# CLK_GEN.net
KiCad netlist of a schematic drawn in Altium Designer
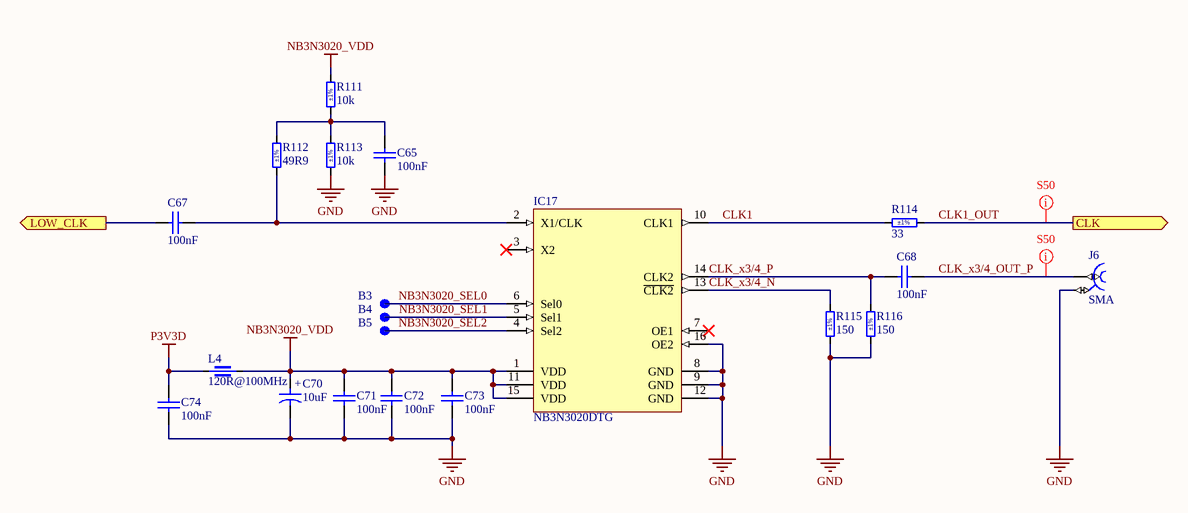
[diagram p0: CLK_GEN.SchDoc]

(export (version "E")
  (design (tool "Eeschema 10.0.6"))
  (components
    (comp (ref "B3")
      (value "SMD Pad")
      (footprint "C100")
      (description "Pad")
      (fields (field (name "PART NUMBER") "SMD_PAD_D1MM") (field (name "AUTHOR") "CERN DEM JLC"))
      (libsource (lib "Eletro-mechanical") (part "Single SMD Pad (Round)"))
    )
    (comp (ref "B4")
      (value "SMD Pad")
      (footprint "C100")
      (description "Pad")
      (fields (field (name "PART NUMBER") "SMD_PAD_D1MM") (field (name "AUTHOR") "CERN DEM JLC"))
      (libsource (lib "Eletro-mechanical") (part "Single SMD Pad (Round)"))
    )
    (comp (ref "B5")
      (value "SMD Pad")
      (footprint "C100")
      (description "Pad")
      (fields (field (name "PART NUMBER") "SMD_PAD_D1MM") (field (name "AUTHOR") "CERN DEM JLC"))
      (libsource (lib "Eletro-mechanical") (part "Single SMD Pad (Round)"))
    )
    (comp (ref "C65")
      (value "100nF")
      (footprint "CAPC1005X55N")
      (description "Non-polarised capacitor")
      (fields
        (field (name "PART NUMBER") "CC0402_100NF_50V_10%_X7R")
        (field (name "VOLTAGE") "50V")
        (field (name "AUTHOR") "CERN DEM MR")
      )
      (libsource (lib "Capacitors") (part "Capacitor - non polarized"))
    )
    (comp (ref "C67")
      (value "100nF")
      (footprint "CAPC1005X55N")
      (description "Non-polarised capacitor")
      (fields
        (field (name "PART NUMBER") "CC0402_100NF_50V_10%_X7R")
        (field (name "VOLTAGE") "50V")
        (field (name "AUTHOR") "CERN DEM MR")
      )
      (libsource (lib "Capacitors") (part "Capacitor - non polarized"))
    )
    (comp (ref "C68")
      (value "100nF")
      (footprint "CAPC1005X55N")
      (description "Non-polarised capacitor")
      (fields
        (field (name "PART NUMBER") "CC0402_100NF_50V_10%_X7R")
        (field (name "VOLTAGE") "50V")
        (field (name "AUTHOR") "CERN DEM MR")
      )
      (libsource (lib "Capacitors") (part "Capacitor - non polarized"))
    )
    (comp (ref "C70")
      (value "10uF")
      (footprint "CAPMP3216X180N")
      (description "Polarised capacitor")
      (fields
        (field (name "PART NUMBER") "CTE3216-18_10UF_16V_20%_AVX_TCJ")
        (field (name "VOLTAGE") "16V")
        (field (name "AUTHOR") "CERN DEM JLC")
      )
      (libsource (lib "Capacitors") (part "Capacitor - polarized"))
    )
    (comp (ref "C71")
      (value "100nF")
      (footprint "CAPC1005X55N")
      (description "Non-polarised capacitor")
      (fields
        (field (name "PART NUMBER") "CC0402_100NF_50V_10%_X7R")
        (field (name "VOLTAGE") "50V")
        (field (name "AUTHOR") "CERN DEM MR")
      )
      (libsource (lib "Capacitors") (part "Capacitor - non polarized"))
    )
    (comp (ref "C72")
      (value "100nF")
      (footprint "CAPC1005X55N")
      (description "Non-polarised capacitor")
      (fields
        (field (name "PART NUMBER") "CC0402_100NF_50V_10%_X7R")
        (field (name "VOLTAGE") "50V")
        (field (name "AUTHOR") "CERN DEM MR")
      )
      (libsource (lib "Capacitors") (part "Capacitor - non polarized"))
    )
    (comp (ref "C73")
      (value "100nF")
      (footprint "CAPC1005X55N")
      (description "Non-polarised capacitor")
      (fields
        (field (name "PART NUMBER") "CC0402_100NF_50V_10%_X7R")
        (field (name "VOLTAGE") "50V")
        (field (name "AUTHOR") "CERN DEM MR")
      )
      (libsource (lib "Capacitors") (part "Capacitor - non polarized"))
    )
    (comp (ref "C74")
      (value "100nF")
      (footprint "CAPC1005X55N")
      (description "Non-polarised capacitor")
      (fields
        (field (name "PART NUMBER") "CC0402_100NF_50V_10%_X7R")
        (field (name "VOLTAGE") "50V")
        (field (name "AUTHOR") "CERN DEM MR")
      )
      (libsource (lib "Capacitors") (part "Capacitor - non polarized"))
    )
    (comp (ref "IC17")
      (value "NB3N3020DTG")
      (footprint "TSOP65P640X120-16N")
      (description "Clock Generator 2MHz to 210MHz Input 210MHz Output 16-Pin TSSOP Tube")
      (fields (field (name "MANUFACTURER") "ON Semiconductor"))
      (libsource (lib "mb") (part "NB3N3020DTG"))
    )
    (comp (ref "J6")
      (value "SMA")
      (footprint "MOLEX_73251-2120")
      (description "50 Ohm, SMA Edge Mount PCB, With Jam Nut And Lock Washer")
      (fields
        (field (name "PART NUMBER") "MOLEX_73251-2120")
        (field (name "MANUFACTURER") "MOLEX")
        (field (name "AUTHOR") "CERN DEM JLC")
      )
      (libsource (lib "mb") (part "CON_SMA_RA_SMD_73251-2120"))
    )
    (comp (ref "L4")
      (value "120R@100MHz")
      (footprint "INDC1608X65N")
      (fields
        (field (name "PART NUMBER") "IND0603_MURATA_BLM18SG121TN1D")
        (field (name "POWER") "3A")
        (field (name "TOLERANCE") "±25%")
        (field (name "AUTHOR") "CERN DEM JLC")
      )
      (libsource (lib "Inductors & Transformers") (part "Ferrite Bead"))
    )
    (comp (ref "R111")
      (value "10k")
      (footprint "RESC1005X40N")
      (description "Resistor - 1%")
      (fields
        (field (name "TOLERANCE") "±1%")
        (field (name "PART NUMBER") "R0402_10K_1%_0.0625W_100PPM")
        (field (name "POWER") "0.0625W")
        (field (name "AUTHOR") "CERN DEM JLC")
      )
      (libsource (lib "Resistors") (part "Resistor - 1%"))
    )
    (comp (ref "R112")
      (value "49R9")
      (footprint "RESC1005X40N")
      (description "Resistor - 1%")
      (fields
        (field (name "TOLERANCE") "±1%")
        (field (name "PART NUMBER") "R0402_49R9_1%_0.0625W_100PPM")
        (field (name "POWER") "0.0625W")
        (field (name "AUTHOR") "CERN DEM JLC")
      )
      (libsource (lib "Resistors") (part "Resistor - 1%"))
    )
    (comp (ref "R113")
      (value "10k")
      (footprint "RESC1005X40N")
      (description "Resistor - 1%")
      (fields
        (field (name "TOLERANCE") "±1%")
        (field (name "PART NUMBER") "R0402_10K_1%_0.0625W_100PPM")
        (field (name "POWER") "0.0625W")
        (field (name "AUTHOR") "CERN DEM JLC")
      )
      (libsource (lib "Resistors") (part "Resistor - 1%"))
    )
    (comp (ref "R114")
      (value "33")
      (footprint "RESC1005X40N")
      (description "Resistor - 1%")
      (fields
        (field (name "TOLERANCE") "±1%")
        (field (name "PART NUMBER") "R0402_33R_1%_0.0625W_100PPM")
        (field (name "POWER") "0.0625W")
        (field (name "AUTHOR") "CERN DEM JLC")
      )
      (libsource (lib "Resistors") (part "Resistor - 1%"))
    )
    (comp (ref "R115")
      (value "150")
      (footprint "RESC1005X40N")
      (description "Resistor - 1%")
      (fields
        (field (name "TOLERANCE") "±1%")
        (field (name "PART NUMBER") "R0402_150R_1%_0.0625W_100PPM")
        (field (name "POWER") "0.0625W")
        (field (name "AUTHOR") "CERN DEM JLC")
      )
      (libsource (lib "Resistors") (part "Resistor - 1%"))
    )
    (comp (ref "R116")
      (value "150")
      (footprint "RESC1005X40N")
      (description "Resistor - 1%")
      (fields
        (field (name "TOLERANCE") "±1%")
        (field (name "PART NUMBER") "R0402_150R_1%_0.0625W_100PPM")
        (field (name "POWER") "0.0625W")
        (field (name "AUTHOR") "CERN DEM JLC")
      )
      (libsource (lib "Resistors") (part "Resistor - 1%"))
    )
  )
  (nets
    (net (code "1") (name "/CLK1") (class "Default")
      (node (ref "IC17") (pin "10") (pinfunction "CLK1_10") (pintype "output"))
      (node (ref "R114") (pin "1") (pinfunction "1_1") (pintype "passive"))
    )
    (net (code "2") (name "/CLK1_OUT") (class "Default")
      (node (ref "R114") (pin "2") (pinfunction "2_2") (pintype "passive"))
    )
    (net (code "3") (name "/CLK_x3{slash}4_N") (class "Default")
      (node (ref "IC17") (pin "13") (pinfunction "~{CLK2}_13") (pintype "output"))
      (node (ref "R115") (pin "2") (pinfunction "2_2") (pintype "passive"))
    )
    (net (code "4") (name "/CLK_x3{slash}4_OUT_P") (class "Default")
      (node (ref "C68") (pin "2") (pinfunction "2_2") (pintype "passive"))
      (node (ref "J6") (pin "1") (pinfunction "1_1") (pintype "bidirectional"))
    )
    (net (code "5") (name "/CLK_x3{slash}4_P") (class "Default")
      (node (ref "C68") (pin "1") (pinfunction "1_1") (pintype "passive"))
      (node (ref "IC17") (pin "14") (pinfunction "CLK2_14") (pintype "output"))
      (node (ref "R116") (pin "2") (pinfunction "2_2") (pintype "passive"))
    )
    (net (code "6") (name "/LOW_CLK") (class "Default")
      (node (ref "C67") (pin "1") (pinfunction "1_1") (pintype "passive"))
    )
    (net (code "7") (name "/NB3N3020_SEL0") (class "Default")
      (node (ref "B3") (pin "1") (pinfunction "1_1") (pintype "bidirectional"))
      (node (ref "IC17") (pin "6") (pinfunction "Sel0_6") (pintype "input"))
    )
    (net (code "8") (name "/NB3N3020_SEL1") (class "Default")
      (node (ref "B4") (pin "1") (pinfunction "1_1") (pintype "bidirectional"))
      (node (ref "IC17") (pin "5") (pinfunction "Sel1_5") (pintype "input"))
    )
    (net (code "9") (name "/NB3N3020_SEL2") (class "Default")
      (node (ref "B5") (pin "1") (pinfunction "1_1") (pintype "bidirectional"))
      (node (ref "IC17") (pin "4") (pinfunction "Sel2_4") (pintype "input"))
    )
    (net (code "10") (name "GND") (class "Default")
      (node (ref "C65") (pin "1") (pinfunction "1_1") (pintype "passive"))
      (node (ref "C70") (pin "2") (pinfunction "2_2") (pintype "passive"))
      (node (ref "C71") (pin "1") (pinfunction "1_1") (pintype "passive"))
      (node (ref "C72") (pin "1") (pinfunction "1_1") (pintype "passive"))
      (node (ref "C73") (pin "1") (pinfunction "1_1") (pintype "passive"))
      (node (ref "C74") (pin "1") (pinfunction "1_1") (pintype "passive"))
      (node (ref "IC17") (pin "12") (pinfunction "GND_12") (pintype "power_in"))
      (node (ref "IC17") (pin "16") (pinfunction "OE2_16") (pintype "input"))
      (node (ref "IC17") (pin "8") (pinfunction "GND_8") (pintype "power_in"))
      (node (ref "IC17") (pin "9") (pinfunction "GND_9") (pintype "power_in"))
      (node (ref "J6") (pin "2") (pinfunction "2_2") (pintype "bidirectional"))
      (node (ref "R113") (pin "1") (pinfunction "1_1") (pintype "passive"))
      (node (ref "R115") (pin "1") (pinfunction "1_1") (pintype "passive"))
      (node (ref "R116") (pin "1") (pinfunction "1_1") (pintype "passive"))
    )
    (net (code "11") (name "NB3N3020_VDD") (class "Default")
      (node (ref "C70") (pin "1") (pinfunction "1_1") (pintype "passive"))
      (node (ref "C71") (pin "2") (pinfunction "2_2") (pintype "passive"))
      (node (ref "C72") (pin "2") (pinfunction "2_2") (pintype "passive"))
      (node (ref "C73") (pin "2") (pinfunction "2_2") (pintype "passive"))
      (node (ref "IC17") (pin "1") (pinfunction "VDD_1") (pintype "power_in"))
      (node (ref "IC17") (pin "11") (pinfunction "VDD_11") (pintype "power_in"))
      (node (ref "IC17") (pin "15") (pinfunction "VDD_15") (pintype "power_in"))
      (node (ref "L4") (pin "2") (pinfunction "2_2") (pintype "passive"))
      (node (ref "R111") (pin "2") (pinfunction "2_2") (pintype "passive"))
    )
    (net (code "12") (name "Net-(C65-Pad2)") (class "Default")
      (node (ref "C65") (pin "2") (pinfunction "2_2") (pintype "passive"))
      (node (ref "R111") (pin "1") (pinfunction "1_1") (pintype "passive"))
      (node (ref "R112") (pin "2") (pinfunction "2_2") (pintype "passive"))
      (node (ref "R113") (pin "2") (pinfunction "2_2") (pintype "passive"))
    )
    (net (code "13") (name "Net-(IC17-X1{slash}CLK)") (class "Default")
      (node (ref "C67") (pin "2") (pinfunction "2_2") (pintype "passive"))
      (node (ref "IC17") (pin "2") (pinfunction "X1/CLK_2") (pintype "input"))
      (node (ref "R112") (pin "1") (pinfunction "1_1") (pintype "passive"))
    )
    (net (code "14") (name "P3V3D") (class "Default")
      (node (ref "C74") (pin "2") (pinfunction "2_2") (pintype "passive"))
      (node (ref "L4") (pin "1") (pinfunction "1_1") (pintype "passive"))
    )
    (net (code "15") (name "unconnected-(IC17-OE1-Pad7)") (class "Default")
      (node (ref "IC17") (pin "7") (pinfunction "OE1_7") (pintype "input+no_connect"))
    )
    (net (code "16") (name "unconnected-(IC17-X2-Pad3)") (class "Default")
      (node (ref "IC17") (pin "3") (pinfunction "X2_3") (pintype "input+no_connect"))
    )
  )
)
